# Xonik_Noise_A6_w_logo_v2_0.net
KiCad netlist of a schematic drawn in EAGLE
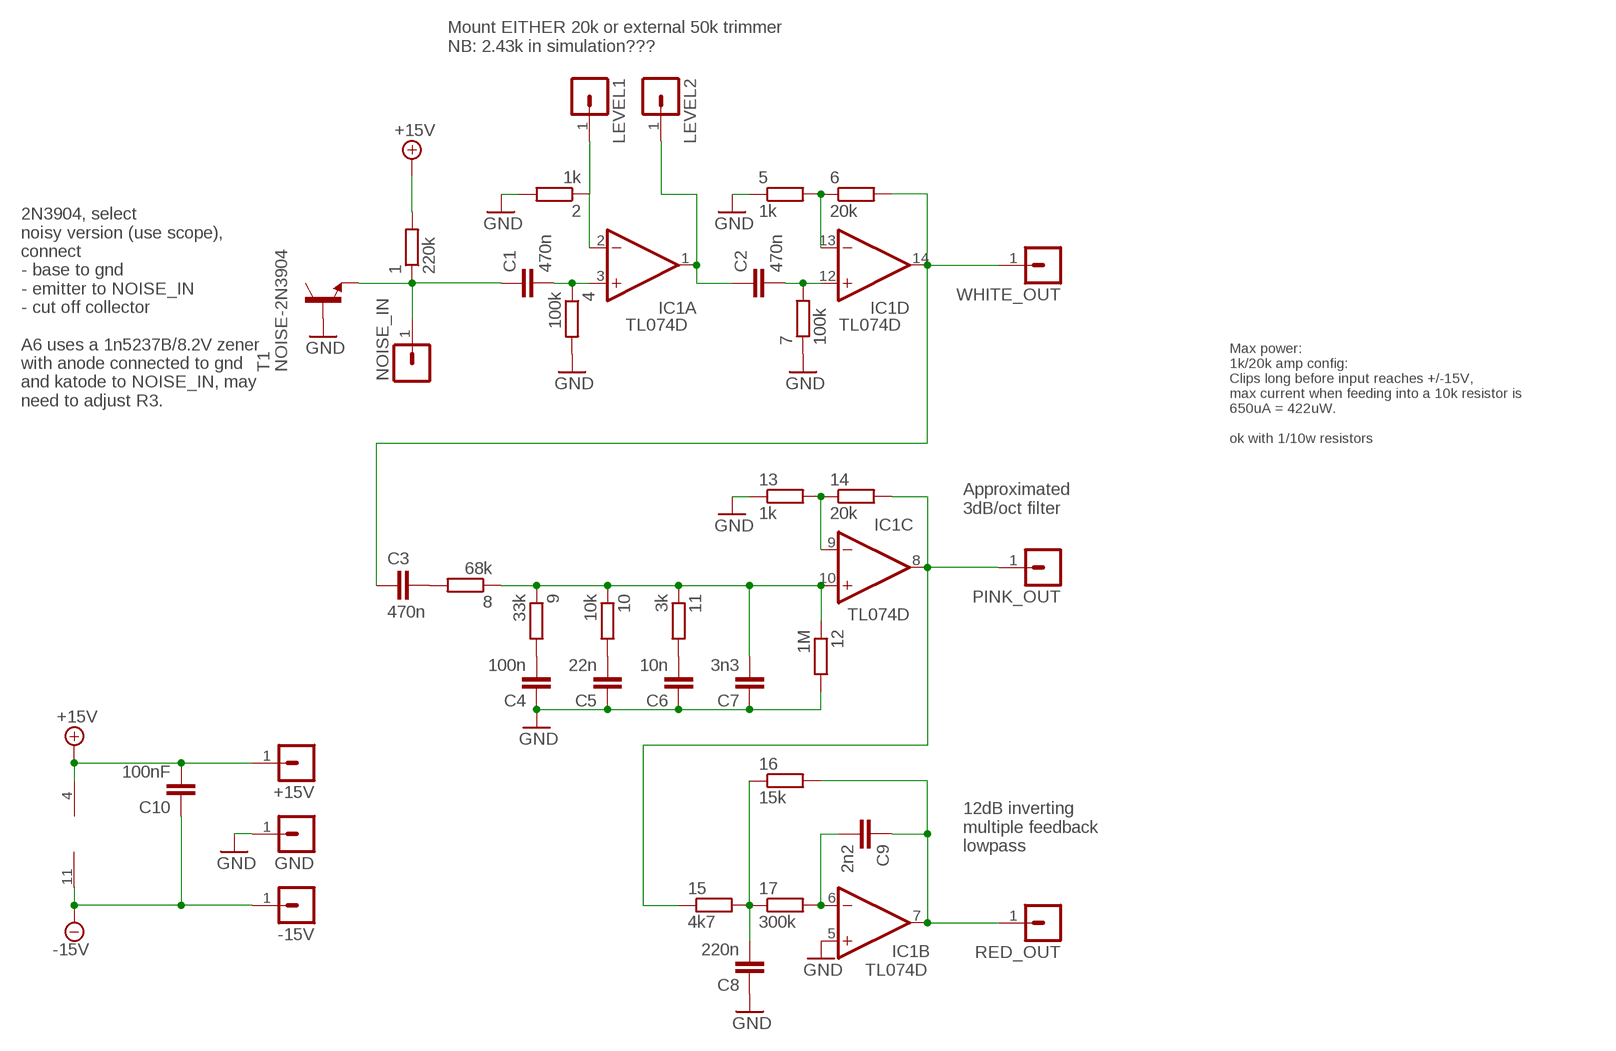
[diagram p0: schematic, sheet 1]

(export (version "E")
  (design (tool "Eeschema 10.0.6"))
  (components
    (comp (ref "+15V")
      (value "MA01-1JP")
      (footprint "eagle-import:SIP-PIN01-1J")
      (libsource (lib "eagle-import") (part "MA01-1JP"))
    )
    (comp (ref "-15V")
      (value "MA01-1JP")
      (footprint "eagle-import:SIP-PIN01-1J")
      (libsource (lib "eagle-import") (part "MA01-1JP"))
    )
    (comp (ref "1")
      (value "220k")
      (footprint "eagle-import:R0805")
      (libsource (lib "eagle-import") (part "R-EU_R0805"))
    )
    (comp (ref "2")
      (value "1k")
      (footprint "eagle-import:R0805")
      (libsource (lib "eagle-import") (part "R-EU_R0805"))
    )
    (comp (ref "4")
      (value "100k")
      (footprint "eagle-import:R0805")
      (libsource (lib "eagle-import") (part "R-EU_R0805"))
    )
    (comp (ref "5")
      (value "1k")
      (footprint "eagle-import:R0805")
      (libsource (lib "eagle-import") (part "R-EU_R0805"))
    )
    (comp (ref "6")
      (value "20k")
      (footprint "eagle-import:R0805")
      (libsource (lib "eagle-import") (part "R-EU_R0805"))
    )
    (comp (ref "7")
      (value "100k")
      (footprint "eagle-import:R0805")
      (libsource (lib "eagle-import") (part "R-EU_R0805"))
    )
    (comp (ref "8")
      (value "68k")
      (footprint "eagle-import:R0805")
      (libsource (lib "eagle-import") (part "R-EU_R0805"))
    )
    (comp (ref "9")
      (value "33k")
      (footprint "eagle-import:R0805")
      (libsource (lib "eagle-import") (part "R-EU_R0805"))
    )
    (comp (ref "10")
      (value "10k")
      (footprint "eagle-import:R0805")
      (libsource (lib "eagle-import") (part "R-EU_R0805"))
    )
    (comp (ref "11")
      (value "3k")
      (footprint "eagle-import:R0805")
      (libsource (lib "eagle-import") (part "R-EU_R0805"))
    )
    (comp (ref "12")
      (value "1M")
      (footprint "eagle-import:R0805")
      (libsource (lib "eagle-import") (part "R-EU_R0805"))
    )
    (comp (ref "13")
      (value "1k")
      (footprint "eagle-import:R0805")
      (libsource (lib "eagle-import") (part "R-EU_R0805"))
    )
    (comp (ref "14")
      (value "20k")
      (footprint "eagle-import:R0805")
      (libsource (lib "eagle-import") (part "R-EU_R0805"))
    )
    (comp (ref "15")
      (value "4k7")
      (footprint "eagle-import:R0805")
      (libsource (lib "eagle-import") (part "R-EU_R0805"))
    )
    (comp (ref "16")
      (value "15k")
      (footprint "eagle-import:R0805")
      (libsource (lib "eagle-import") (part "R-EU_R0805"))
    )
    (comp (ref "17")
      (value "300k")
      (footprint "eagle-import:R0805")
      (libsource (lib "eagle-import") (part "R-EU_R0805"))
    )
    (comp (ref "C1")
      (value "470n")
      (footprint "eagle-import:C0805")
      (libsource (lib "eagle-import") (part "C-EUC0805"))
    )
    (comp (ref "C2")
      (value "470n")
      (footprint "eagle-import:C0805")
      (libsource (lib "eagle-import") (part "C-EUC0805"))
    )
    (comp (ref "C3")
      (value "470n")
      (footprint "eagle-import:C0805")
      (libsource (lib "eagle-import") (part "C-EUC0805"))
    )
    (comp (ref "C4")
      (value "100n")
      (footprint "eagle-import:C0805")
      (libsource (lib "eagle-import") (part "C-EUC0805"))
    )
    (comp (ref "C5")
      (value "22n")
      (footprint "eagle-import:C0805")
      (libsource (lib "eagle-import") (part "C-EUC0805"))
    )
    (comp (ref "C6")
      (value "10n")
      (footprint "eagle-import:C0805")
      (libsource (lib "eagle-import") (part "C-EUC0805"))
    )
    (comp (ref "C7")
      (value "3n3")
      (footprint "eagle-import:C0805")
      (libsource (lib "eagle-import") (part "C-EUC0805"))
    )
    (comp (ref "C8")
      (value "220n")
      (footprint "eagle-import:C0805")
      (libsource (lib "eagle-import") (part "C-EUC0805"))
    )
    (comp (ref "C9")
      (value "2n2")
      (footprint "eagle-import:C0805")
      (libsource (lib "eagle-import") (part "C-EUC0805"))
    )
    (comp (ref "C10")
      (value "100nF")
      (footprint "eagle-import:C0603")
      (libsource (lib "eagle-import") (part "C-EUC0603"))
    )
    (comp (ref "GND")
      (value "MA01-1JP")
      (footprint "eagle-import:SIP-PIN01-1J")
      (libsource (lib "eagle-import") (part "MA01-1JP"))
    )
    (comp (ref "IC1")
      (value "TL074D")
      (footprint "eagle-import:SO14")
      (libsource (lib "eagle-import") (part "TL074D"))
    )
    (comp (ref "LEVEL1")
      (value "MA01-1JP")
      (footprint "eagle-import:SIP-PIN01-1J")
      (libsource (lib "eagle-import") (part "MA01-1JP"))
    )
    (comp (ref "LEVEL2")
      (value "MA01-1JP")
      (footprint "eagle-import:SIP-PIN01-1J")
      (libsource (lib "eagle-import") (part "MA01-1JP"))
    )
    (comp (ref "NOISE_IN")
      (value "MA01-1JP")
      (footprint "eagle-import:SIP-PIN01-1J")
      (libsource (lib "eagle-import") (part "MA01-1JP"))
    )
    (comp (ref "PINK_OUT")
      (value "MA01-1JP")
      (footprint "eagle-import:SIP-PIN01-1J")
      (libsource (lib "eagle-import") (part "MA01-1JP"))
    )
    (comp (ref "RED_OUT")
      (value "MA01-1JP")
      (footprint "eagle-import:SIP-PIN01-1J")
      (libsource (lib "eagle-import") (part "MA01-1JP"))
    )
    (comp (ref "T1")
      (value "NOISE-2N3904")
      (footprint "eagle-import:NOISE-2N3904-J")
      (libsource (lib "eagle-import") (part "NOISE-2N3904"))
    )
    (comp (ref "WHITE_OUT")
      (value "MA01-1JP")
      (footprint "eagle-import:SIP-PIN01-1J")
      (libsource (lib "eagle-import") (part "MA01-1JP"))
    )
  )
  (nets
    (net (code "1") (name "+15V") (class "Default")
      (node (ref "+15V") (pin "1") (pinfunction "1_1") (pintype "passive"))
      (node (ref "1") (pin "2") (pinfunction "2_2") (pintype "passive"))
      (node (ref "C10") (pin "2") (pinfunction "2_2") (pintype "passive"))
      (node (ref "IC1") (pin "4") (pinfunction "V+_4") (pintype "power_in"))
    )
    (net (code "2") (name "-15V") (class "Default")
      (node (ref "-15V") (pin "1") (pinfunction "1_1") (pintype "passive"))
      (node (ref "C10") (pin "1") (pinfunction "1_1") (pintype "passive"))
      (node (ref "IC1") (pin "11") (pinfunction "V-_11") (pintype "power_in"))
    )
    (net (code "3") (name "GND") (class "Default")
      (node (ref "12") (pin "2") (pinfunction "2_2") (pintype "passive"))
      (node (ref "13") (pin "1") (pinfunction "1_1") (pintype "passive"))
      (node (ref "2") (pin "2") (pinfunction "2_2") (pintype "passive"))
      (node (ref "4") (pin "2") (pinfunction "2_2") (pintype "passive"))
      (node (ref "5") (pin "1") (pinfunction "1_1") (pintype "passive"))
      (node (ref "7") (pin "1") (pinfunction "1_1") (pintype "passive"))
      (node (ref "C4") (pin "1") (pinfunction "1_1") (pintype "passive"))
      (node (ref "C5") (pin "1") (pinfunction "1_1") (pintype "passive"))
      (node (ref "C6") (pin "1") (pinfunction "1_1") (pintype "passive"))
      (node (ref "C7") (pin "1") (pinfunction "1_1") (pintype "passive"))
      (node (ref "C8") (pin "1") (pinfunction "1_1") (pintype "passive"))
      (node (ref "GND") (pin "1") (pinfunction "1_1") (pintype "passive"))
      (node (ref "IC1") (pin "5") (pinfunction "+IN_5") (pintype "input"))
      (node (ref "T1") (pin "B") (pinfunction "B_B") (pintype "passive"))
    )
    (net (code "4") (name "Net-(1-Pad1)") (class "Default")
      (node (ref "1") (pin "1") (pinfunction "1_1") (pintype "passive"))
      (node (ref "C1") (pin "1") (pinfunction "1_1") (pintype "passive"))
      (node (ref "NOISE_IN") (pin "1") (pinfunction "1_1") (pintype "passive"))
      (node (ref "T1") (pin "E") (pinfunction "E_E") (pintype "passive"))
    )
    (net (code "5") (name "Net-(8-Pad2)") (class "Default")
      (node (ref "8") (pin "2") (pinfunction "2_2") (pintype "passive"))
      (node (ref "C3") (pin "2") (pinfunction "2_2") (pintype "passive"))
    )
    (net (code "6") (name "Net-(9-Pad2)") (class "Default")
      (node (ref "9") (pin "2") (pinfunction "2_2") (pintype "passive"))
      (node (ref "C4") (pin "2") (pinfunction "2_2") (pintype "passive"))
    )
    (net (code "7") (name "Net-(10-Pad2)") (class "Default")
      (node (ref "10") (pin "2") (pinfunction "2_2") (pintype "passive"))
      (node (ref "C5") (pin "2") (pinfunction "2_2") (pintype "passive"))
    )
    (net (code "8") (name "Net-(11-Pad2)") (class "Default")
      (node (ref "11") (pin "2") (pinfunction "2_2") (pintype "passive"))
      (node (ref "C6") (pin "2") (pinfunction "2_2") (pintype "passive"))
    )
    (net (code "9") (name "Net-(15-Pad2)") (class "Default")
      (node (ref "15") (pin "2") (pinfunction "2_2") (pintype "passive"))
      (node (ref "16") (pin "1") (pinfunction "1_1") (pintype "passive"))
      (node (ref "17") (pin "1") (pinfunction "1_1") (pintype "passive"))
      (node (ref "C8") (pin "2") (pinfunction "2_2") (pintype "passive"))
    )
    (net (code "10") (name "Net-(IC1A-+IN)") (class "Default")
      (node (ref "4") (pin "1") (pinfunction "1_1") (pintype "passive"))
      (node (ref "C1") (pin "2") (pinfunction "2_2") (pintype "passive"))
      (node (ref "IC1") (pin "3") (pinfunction "+IN_3") (pintype "input"))
    )
    (net (code "11") (name "Net-(IC1A--IN)") (class "Default")
      (node (ref "2") (pin "1") (pinfunction "1_1") (pintype "passive"))
      (node (ref "IC1") (pin "2") (pinfunction "-IN_2") (pintype "input"))
      (node (ref "LEVEL1") (pin "1") (pinfunction "1_1") (pintype "passive"))
    )
    (net (code "12") (name "Net-(IC1A-OUT)") (class "Default")
      (node (ref "C2") (pin "1") (pinfunction "1_1") (pintype "passive"))
      (node (ref "IC1") (pin "1") (pinfunction "OUT_1") (pintype "output"))
      (node (ref "LEVEL2") (pin "1") (pinfunction "1_1") (pintype "passive"))
    )
    (net (code "13") (name "Net-(IC1B--IN)") (class "Default")
      (node (ref "17") (pin "2") (pinfunction "2_2") (pintype "passive"))
      (node (ref "C9") (pin "2") (pinfunction "2_2") (pintype "passive"))
      (node (ref "IC1") (pin "6") (pinfunction "-IN_6") (pintype "input"))
    )
    (net (code "14") (name "Net-(IC1B-OUT)") (class "Default")
      (node (ref "16") (pin "2") (pinfunction "2_2") (pintype "passive"))
      (node (ref "C9") (pin "1") (pinfunction "1_1") (pintype "passive"))
      (node (ref "IC1") (pin "7") (pinfunction "OUT_7") (pintype "output"))
      (node (ref "RED_OUT") (pin "1") (pinfunction "1_1") (pintype "passive"))
    )
    (net (code "15") (name "Net-(IC1C-+IN)") (class "Default")
      (node (ref "10") (pin "1") (pinfunction "1_1") (pintype "passive"))
      (node (ref "11") (pin "1") (pinfunction "1_1") (pintype "passive"))
      (node (ref "12") (pin "1") (pinfunction "1_1") (pintype "passive"))
      (node (ref "8") (pin "1") (pinfunction "1_1") (pintype "passive"))
      (node (ref "9") (pin "1") (pinfunction "1_1") (pintype "passive"))
      (node (ref "C7") (pin "2") (pinfunction "2_2") (pintype "passive"))
      (node (ref "IC1") (pin "10") (pinfunction "+IN_10") (pintype "input"))
    )
    (net (code "16") (name "Net-(IC1C--IN)") (class "Default")
      (node (ref "13") (pin "2") (pinfunction "2_2") (pintype "passive"))
      (node (ref "14") (pin "1") (pinfunction "1_1") (pintype "passive"))
      (node (ref "IC1") (pin "9") (pinfunction "-IN_9") (pintype "input"))
    )
    (net (code "17") (name "Net-(IC1C-OUT)") (class "Default")
      (node (ref "14") (pin "2") (pinfunction "2_2") (pintype "passive"))
      (node (ref "15") (pin "1") (pinfunction "1_1") (pintype "passive"))
      (node (ref "IC1") (pin "8") (pinfunction "OUT_8") (pintype "output"))
      (node (ref "PINK_OUT") (pin "1") (pinfunction "1_1") (pintype "passive"))
    )
    (net (code "18") (name "Net-(IC1D-+IN)") (class "Default")
      (node (ref "7") (pin "2") (pinfunction "2_2") (pintype "passive"))
      (node (ref "C2") (pin "2") (pinfunction "2_2") (pintype "passive"))
      (node (ref "IC1") (pin "12") (pinfunction "+IN_12") (pintype "input"))
    )
    (net (code "19") (name "Net-(IC1D--IN)") (class "Default")
      (node (ref "5") (pin "2") (pinfunction "2_2") (pintype "passive"))
      (node (ref "6") (pin "1") (pinfunction "1_1") (pintype "passive"))
      (node (ref "IC1") (pin "13") (pinfunction "-IN_13") (pintype "input"))
    )
    (net (code "20") (name "Net-(IC1D-OUT)") (class "Default")
      (node (ref "6") (pin "2") (pinfunction "2_2") (pintype "passive"))
      (node (ref "C3") (pin "1") (pinfunction "1_1") (pintype "passive"))
      (node (ref "IC1") (pin "14") (pinfunction "OUT_14") (pintype "output"))
      (node (ref "WHITE_OUT") (pin "1") (pinfunction "1_1") (pintype "passive"))
    )
  )
)
